# RAY_shield_V4.net
KiCad netlist of a schematic drawn in EAGLE
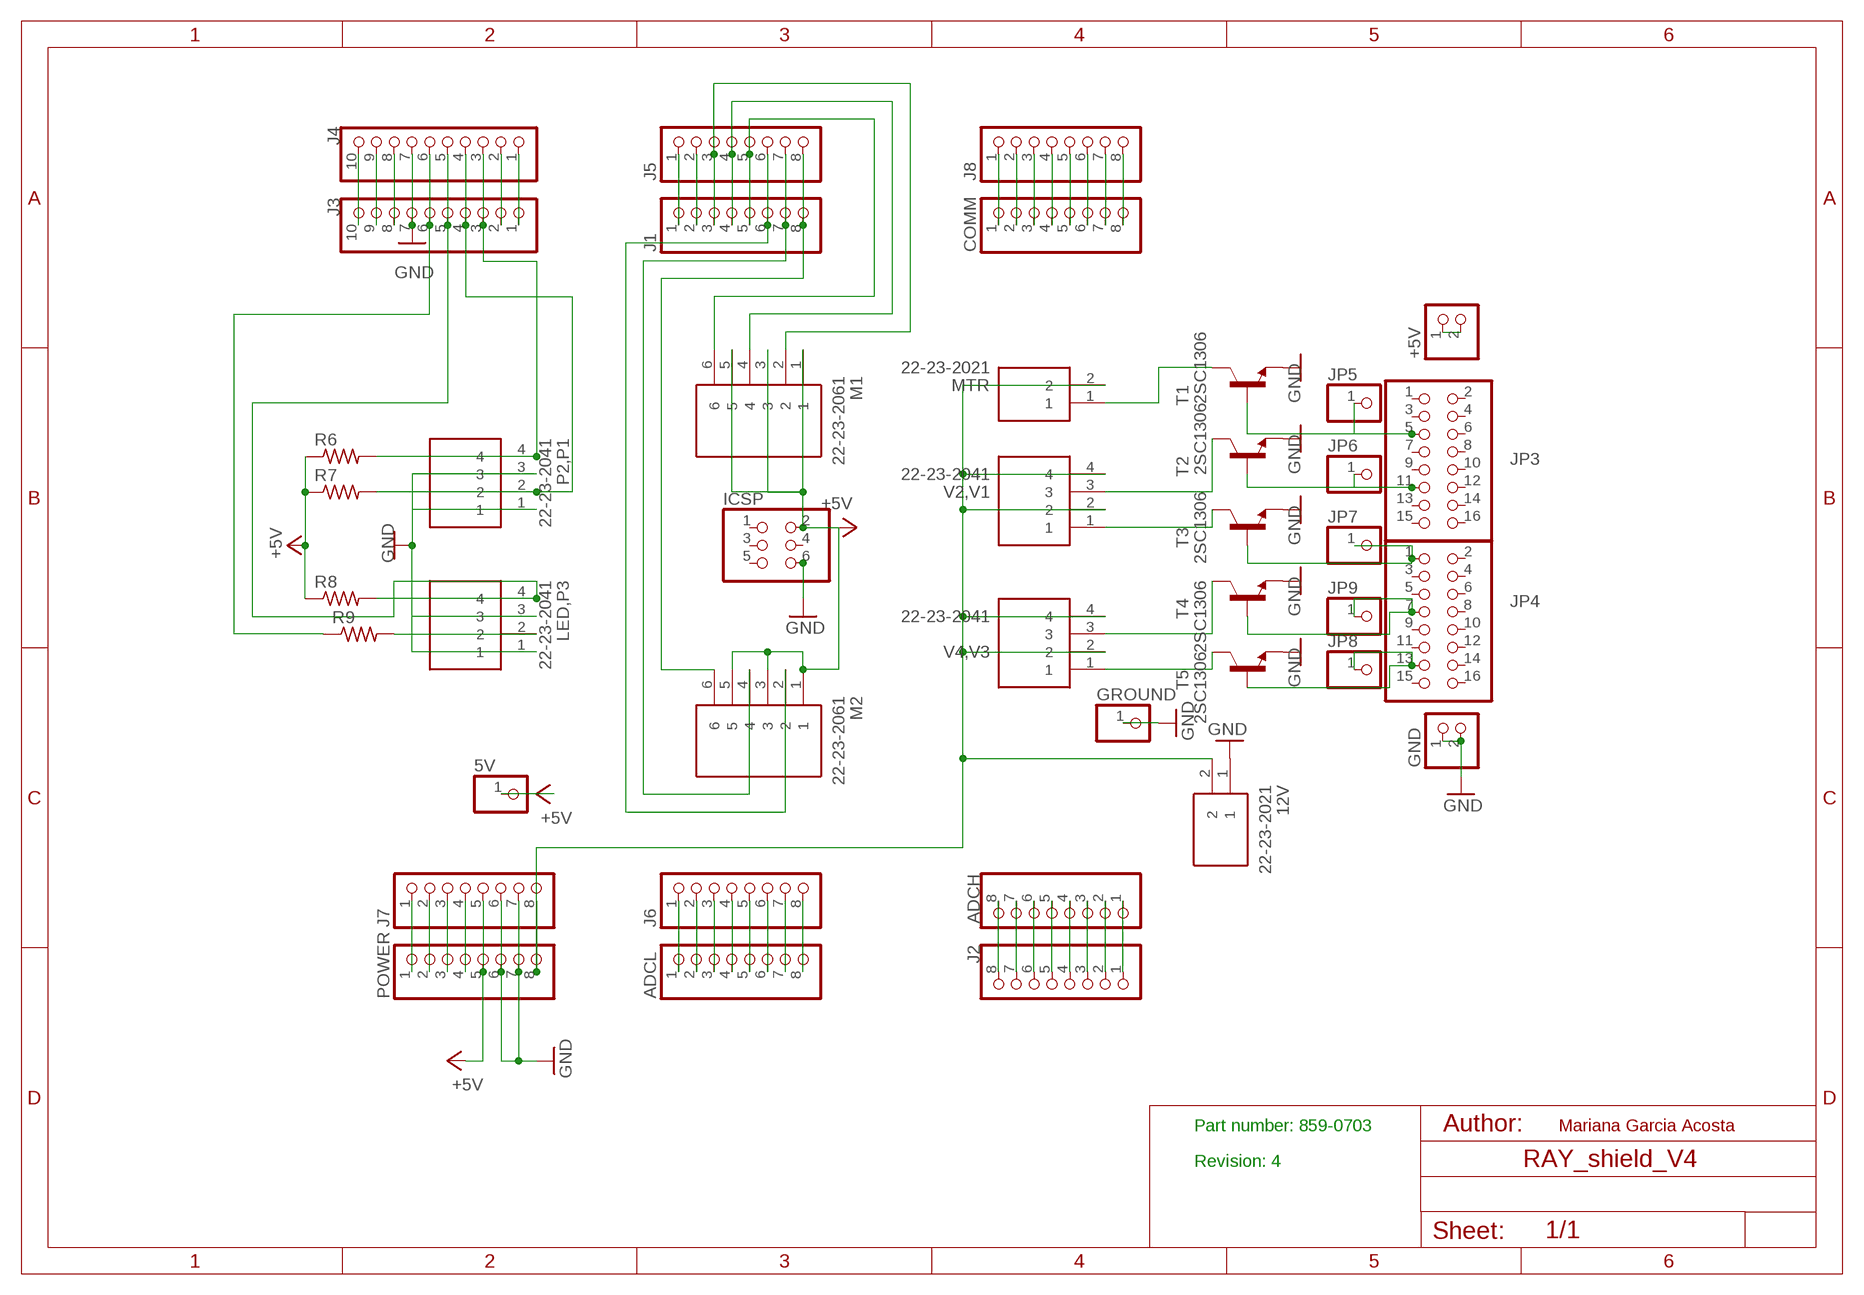
[diagram p0: schematic, sheet 1]

(export (version "E")
  (design (tool "Eeschema 10.0.6"))
  (components
    (comp (ref "+5V")
      (value "PINHD-1X2")
      (footprint "eagle-import:1X02")
      (libsource (lib "eagle-import") (part "PINHD-1X2"))
    )
    (comp (ref "5V")
      (value "PINHD-1X1")
      (footprint "eagle-import:1X01")
      (libsource (lib "eagle-import") (part "PINHD-1X1"))
    )
    (comp (ref "12V")
      (value "22-23-2021")
      (footprint "eagle-import:SHDR2W87P0X254_1X2_493X635X110")
      (fields (field (name "MOUSER_PART_NUMBER") "538-22-23-2021"))
      (libsource (lib "eagle-import") (part "22-23-2021"))
    )
    (comp (ref "ADCH")
      (value "PINHD-1X8TH")
      (footprint "eagle-import:1X08-TH")
      (libsource (lib "eagle-import") (part "PINHD-1X8TH"))
    )
    (comp (ref "ADCL")
      (value "PINHD-1X8TH")
      (footprint "eagle-import:1X08-TH")
      (libsource (lib "eagle-import") (part "PINHD-1X8TH"))
    )
    (comp (ref "COMM")
      (value "PINHD-1X8TH")
      (footprint "eagle-import:1X08-TH")
      (libsource (lib "eagle-import") (part "PINHD-1X8TH"))
    )
    (comp (ref "GND")
      (value "PINHD-1X2")
      (footprint "eagle-import:1X02")
      (libsource (lib "eagle-import") (part "PINHD-1X2"))
    )
    (comp (ref "GROUND")
      (value "PINHD-1X1")
      (footprint "eagle-import:1X01")
      (libsource (lib "eagle-import") (part "PINHD-1X1"))
    )
    (comp (ref "ICSP")
      (value "PINHD-2X3")
      (footprint "eagle-import:2X03")
      (libsource (lib "eagle-import") (part "PINHD-2X3"))
    )
    (comp (ref "J1")
      (value "PINHD-1X8TH")
      (footprint "eagle-import:1X08-TH")
      (libsource (lib "eagle-import") (part "PINHD-1X8TH"))
    )
    (comp (ref "J2")
      (value "PINHD-1X8TH")
      (footprint "eagle-import:1X08-TH")
      (libsource (lib "eagle-import") (part "PINHD-1X8TH"))
    )
    (comp (ref "J3")
      (value "PINHD-1X10TH")
      (footprint "eagle-import:1X10-TH")
      (libsource (lib "eagle-import") (part "PINHD-1X10TH"))
    )
    (comp (ref "J4")
      (value "PINHD-1X10TH")
      (footprint "eagle-import:1X10-TH")
      (libsource (lib "eagle-import") (part "PINHD-1X10TH"))
    )
    (comp (ref "J5")
      (value "PINHD-1X8TH")
      (footprint "eagle-import:1X08-TH")
      (libsource (lib "eagle-import") (part "PINHD-1X8TH"))
    )
    (comp (ref "J6")
      (value "PINHD-1X8TH")
      (footprint "eagle-import:1X08-TH")
      (libsource (lib "eagle-import") (part "PINHD-1X8TH"))
    )
    (comp (ref "J7")
      (value "PINHD-1X8TH")
      (footprint "eagle-import:1X08-TH")
      (libsource (lib "eagle-import") (part "PINHD-1X8TH"))
    )
    (comp (ref "J8")
      (value "PINHD-1X8TH")
      (footprint "eagle-import:1X08-TH")
      (libsource (lib "eagle-import") (part "PINHD-1X8TH"))
    )
    (comp (ref "JP3")
      (value "PINHD-2X8")
      (footprint "eagle-import:2X08")
      (libsource (lib "eagle-import") (part "PINHD-2X8"))
    )
    (comp (ref "JP4")
      (value "PINHD-2X8")
      (footprint "eagle-import:2X08")
      (libsource (lib "eagle-import") (part "PINHD-2X8"))
    )
    (comp (ref "JP5")
      (value "PINHD-1X1")
      (footprint "eagle-import:1X01")
      (libsource (lib "eagle-import") (part "PINHD-1X1"))
    )
    (comp (ref "JP6")
      (value "PINHD-1X1")
      (footprint "eagle-import:1X01")
      (libsource (lib "eagle-import") (part "PINHD-1X1"))
    )
    (comp (ref "JP7")
      (value "PINHD-1X1")
      (footprint "eagle-import:1X01")
      (libsource (lib "eagle-import") (part "PINHD-1X1"))
    )
    (comp (ref "JP8")
      (value "PINHD-1X1")
      (footprint "eagle-import:1X01")
      (libsource (lib "eagle-import") (part "PINHD-1X1"))
    )
    (comp (ref "JP9")
      (value "PINHD-1X1")
      (footprint "eagle-import:1X01")
      (libsource (lib "eagle-import") (part "PINHD-1X1"))
    )
    (comp (ref "LED,P3")
      (value "22-23-2041")
      (footprint "eagle-import:SHDR4W87P0X254_1X4_1001X635X11")
      (fields (field (name "MOUSER_PART_NUMBER") "538-22-23-2041"))
      (libsource (lib "eagle-import") (part "22-23-2041"))
    )
    (comp (ref "M1")
      (value "22-23-2061")
      (footprint "eagle-import:SHDR6W87P0X254_1X6_1509X635X11")
      (fields (field (name "MOUSER_PART_NUMBER") "538-22-23-2061"))
      (libsource (lib "eagle-import") (part "22-23-2061"))
    )
    (comp (ref "M2")
      (value "22-23-2061")
      (footprint "eagle-import:SHDR6W87P0X254_1X6_1509X635X11")
      (fields (field (name "MOUSER_PART_NUMBER") "538-22-23-2061"))
      (libsource (lib "eagle-import") (part "22-23-2061"))
    )
    (comp (ref "MTR")
      (value "22-23-2021")
      (footprint "eagle-import:SHDR2W87P0X254_1X2_493X635X110")
      (fields (field (name "MOUSER_PART_NUMBER") "538-22-23-2021"))
      (libsource (lib "eagle-import") (part "22-23-2021"))
    )
    (comp (ref "P2,P1")
      (value "22-23-2041")
      (footprint "eagle-import:SHDR4W87P0X254_1X4_1001X635X11")
      (fields (field (name "MOUSER_PART_NUMBER") "538-22-23-2041"))
      (libsource (lib "eagle-import") (part "22-23-2041"))
    )
    (comp (ref "POWER")
      (value "PINHD-1X8TH")
      (footprint "eagle-import:1X08-TH")
      (libsource (lib "eagle-import") (part "PINHD-1X8TH"))
    )
    (comp (ref "R6")
      (value "R-US_0207/7")
      (footprint "eagle-import:0207_7")
      (libsource (lib "eagle-import") (part "R-US_0207/7"))
    )
    (comp (ref "R7")
      (value "R-US_0207/7")
      (footprint "eagle-import:0207_7")
      (libsource (lib "eagle-import") (part "R-US_0207/7"))
    )
    (comp (ref "R8")
      (value "R-US_0207/7")
      (footprint "eagle-import:0207_7")
      (libsource (lib "eagle-import") (part "R-US_0207/7"))
    )
    (comp (ref "R9")
      (value "R-US_0207/7")
      (footprint "eagle-import:0207_7")
      (libsource (lib "eagle-import") (part "R-US_0207/7"))
    )
    (comp (ref "T1")
      (value "2SC1306")
      (footprint "eagle-import:TO220BV")
      (libsource (lib "eagle-import") (part "2SC1306"))
    )
    (comp (ref "T2")
      (value "2SC1306")
      (footprint "eagle-import:TO220BV")
      (libsource (lib "eagle-import") (part "2SC1306"))
    )
    (comp (ref "T3")
      (value "2SC1306")
      (footprint "eagle-import:TO220BV")
      (libsource (lib "eagle-import") (part "2SC1306"))
    )
    (comp (ref "T4")
      (value "2SC1306")
      (footprint "eagle-import:TO220BV")
      (libsource (lib "eagle-import") (part "2SC1306"))
    )
    (comp (ref "T5")
      (value "2SC1306")
      (footprint "eagle-import:TO220BV")
      (libsource (lib "eagle-import") (part "2SC1306"))
    )
    (comp (ref "V2,V1")
      (value "22-23-2041")
      (footprint "eagle-import:SHDR4W87P0X254_1X4_1001X635X11")
      (fields (field (name "MOUSER_PART_NUMBER") "538-22-23-2041"))
      (libsource (lib "eagle-import") (part "22-23-2041"))
    )
    (comp (ref "V4,V3")
      (value "22-23-2041")
      (footprint "eagle-import:SHDR4W87P0X254_1X4_1001X635X11")
      (fields (field (name "MOUSER_PART_NUMBER") "538-22-23-2041"))
      (libsource (lib "eagle-import") (part "22-23-2041"))
    )
  )
  (nets
    (net (code "1") (name "+5V") (class "Default")
      (node (ref "5V") (pin "1") (pinfunction "1_1") (pintype "passive"))
      (node (ref "ICSP") (pin "2") (pinfunction "2_2") (pintype "passive"))
      (node (ref "J7") (pin "5") (pinfunction "5_5") (pintype "passive"))
      (node (ref "M1") (pin "1") (pinfunction "1_1") (pintype "bidirectional"))
      (node (ref "M1") (pin "3") (pinfunction "3_3") (pintype "bidirectional"))
      (node (ref "M1") (pin "5") (pinfunction "5_5") (pintype "bidirectional"))
      (node (ref "M2") (pin "1") (pinfunction "1_1") (pintype "bidirectional"))
      (node (ref "M2") (pin "3") (pinfunction "3_3") (pintype "bidirectional"))
      (node (ref "M2") (pin "5") (pinfunction "5_5") (pintype "bidirectional"))
      (node (ref "POWER") (pin "5") (pinfunction "5_5") (pintype "passive"))
      (node (ref "R6") (pin "1") (pinfunction "1_1") (pintype "passive"))
      (node (ref "R7") (pin "1") (pinfunction "1_1") (pintype "passive"))
      (node (ref "R8") (pin "1") (pinfunction "1_1") (pintype "passive"))
    )
    (net (code "2") (name "GND") (class "Default")
      (node (ref "12V") (pin "1") (pinfunction "1_1") (pintype "bidirectional"))
      (node (ref "GND") (pin "1") (pinfunction "1_1") (pintype "passive"))
      (node (ref "GND") (pin "2") (pinfunction "2_2") (pintype "passive"))
      (node (ref "GROUND") (pin "1") (pinfunction "1_1") (pintype "passive"))
      (node (ref "ICSP") (pin "6") (pinfunction "6_6") (pintype "passive"))
      (node (ref "J3") (pin "7") (pinfunction "7_7") (pintype "passive"))
      (node (ref "J4") (pin "7") (pinfunction "7_7") (pintype "passive"))
      (node (ref "J7") (pin "6") (pinfunction "6_6") (pintype "passive"))
      (node (ref "J7") (pin "7") (pinfunction "7_7") (pintype "passive"))
      (node (ref "LED,P3") (pin "1") (pinfunction "1_1") (pintype "bidirectional"))
      (node (ref "LED,P3") (pin "3") (pinfunction "3_3") (pintype "bidirectional"))
      (node (ref "P2,P1") (pin "1") (pinfunction "1_1") (pintype "bidirectional"))
      (node (ref "P2,P1") (pin "3") (pinfunction "3_3") (pintype "bidirectional"))
      (node (ref "POWER") (pin "6") (pinfunction "6_6") (pintype "passive"))
      (node (ref "POWER") (pin "7") (pinfunction "7_7") (pintype "passive"))
      (node (ref "T1") (pin "3") (pinfunction "E_3") (pintype "passive"))
      (node (ref "T2") (pin "3") (pinfunction "E_3") (pintype "passive"))
      (node (ref "T3") (pin "3") (pinfunction "E_3") (pintype "passive"))
      (node (ref "T4") (pin "3") (pinfunction "E_3") (pintype "passive"))
      (node (ref "T5") (pin "3") (pinfunction "E_3") (pintype "passive"))
    )
    (net (code "3") (name "Net-(+5V-Pad1)") (class "Default")
      (node (ref "+5V") (pin "1") (pinfunction "1_1") (pintype "passive"))
      (node (ref "+5V") (pin "2") (pinfunction "2_2") (pintype "passive"))
    )
    (net (code "4") (name "Net-(12V-Pad2)") (class "Default")
      (node (ref "12V") (pin "2") (pinfunction "2_2") (pintype "bidirectional"))
      (node (ref "J7") (pin "8") (pinfunction "8_8") (pintype "passive"))
      (node (ref "MTR") (pin "2") (pinfunction "2_2") (pintype "bidirectional"))
      (node (ref "POWER") (pin "8") (pinfunction "8_8") (pintype "passive"))
      (node (ref "V2,V1") (pin "2") (pinfunction "2_2") (pintype "bidirectional"))
      (node (ref "V2,V1") (pin "4") (pinfunction "4_4") (pintype "bidirectional"))
      (node (ref "V4,V3") (pin "2") (pinfunction "2_2") (pintype "bidirectional"))
      (node (ref "V4,V3") (pin "4") (pinfunction "4_4") (pintype "bidirectional"))
    )
    (net (code "5") (name "Net-(ADCH-Pad1)") (class "Default")
      (node (ref "ADCH") (pin "1") (pinfunction "1_1") (pintype "passive"))
      (node (ref "J2") (pin "1") (pinfunction "1_1") (pintype "passive"))
    )
    (net (code "6") (name "Net-(ADCH-Pad2)") (class "Default")
      (node (ref "ADCH") (pin "2") (pinfunction "2_2") (pintype "passive"))
      (node (ref "J2") (pin "2") (pinfunction "2_2") (pintype "passive"))
    )
    (net (code "7") (name "Net-(ADCH-Pad3)") (class "Default")
      (node (ref "ADCH") (pin "3") (pinfunction "3_3") (pintype "passive"))
      (node (ref "J2") (pin "3") (pinfunction "3_3") (pintype "passive"))
    )
    (net (code "8") (name "Net-(ADCH-Pad4)") (class "Default")
      (node (ref "ADCH") (pin "4") (pinfunction "4_4") (pintype "passive"))
      (node (ref "J2") (pin "4") (pinfunction "4_4") (pintype "passive"))
    )
    (net (code "9") (name "Net-(ADCH-Pad5)") (class "Default")
      (node (ref "ADCH") (pin "5") (pinfunction "5_5") (pintype "passive"))
      (node (ref "J2") (pin "5") (pinfunction "5_5") (pintype "passive"))
    )
    (net (code "10") (name "Net-(ADCH-Pad6)") (class "Default")
      (node (ref "ADCH") (pin "6") (pinfunction "6_6") (pintype "passive"))
      (node (ref "J2") (pin "6") (pinfunction "6_6") (pintype "passive"))
    )
    (net (code "11") (name "Net-(ADCH-Pad7)") (class "Default")
      (node (ref "ADCH") (pin "7") (pinfunction "7_7") (pintype "passive"))
      (node (ref "J2") (pin "7") (pinfunction "7_7") (pintype "passive"))
    )
    (net (code "12") (name "Net-(ADCH-Pad8)") (class "Default")
      (node (ref "ADCH") (pin "8") (pinfunction "8_8") (pintype "passive"))
      (node (ref "J2") (pin "8") (pinfunction "8_8") (pintype "passive"))
    )
    (net (code "13") (name "Net-(ADCL-Pad1)") (class "Default")
      (node (ref "ADCL") (pin "1") (pinfunction "1_1") (pintype "passive"))
      (node (ref "J6") (pin "1") (pinfunction "1_1") (pintype "passive"))
    )
    (net (code "14") (name "Net-(ADCL-Pad2)") (class "Default")
      (node (ref "ADCL") (pin "2") (pinfunction "2_2") (pintype "passive"))
      (node (ref "J6") (pin "2") (pinfunction "2_2") (pintype "passive"))
    )
    (net (code "15") (name "Net-(ADCL-Pad3)") (class "Default")
      (node (ref "ADCL") (pin "3") (pinfunction "3_3") (pintype "passive"))
      (node (ref "J6") (pin "3") (pinfunction "3_3") (pintype "passive"))
    )
    (net (code "16") (name "Net-(ADCL-Pad4)") (class "Default")
      (node (ref "ADCL") (pin "4") (pinfunction "4_4") (pintype "passive"))
      (node (ref "J6") (pin "4") (pinfunction "4_4") (pintype "passive"))
    )
    (net (code "17") (name "Net-(ADCL-Pad5)") (class "Default")
      (node (ref "ADCL") (pin "5") (pinfunction "5_5") (pintype "passive"))
      (node (ref "J6") (pin "5") (pinfunction "5_5") (pintype "passive"))
    )
    (net (code "18") (name "Net-(ADCL-Pad6)") (class "Default")
      (node (ref "ADCL") (pin "6") (pinfunction "6_6") (pintype "passive"))
      (node (ref "J6") (pin "6") (pinfunction "6_6") (pintype "passive"))
    )
    (net (code "19") (name "Net-(ADCL-Pad7)") (class "Default")
      (node (ref "ADCL") (pin "7") (pinfunction "7_7") (pintype "passive"))
      (node (ref "J6") (pin "7") (pinfunction "7_7") (pintype "passive"))
    )
    (net (code "20") (name "Net-(ADCL-Pad8)") (class "Default")
      (node (ref "ADCL") (pin "8") (pinfunction "8_8") (pintype "passive"))
      (node (ref "J6") (pin "8") (pinfunction "8_8") (pintype "passive"))
    )
    (net (code "21") (name "Net-(COMM-Pad1)") (class "Default")
      (node (ref "COMM") (pin "1") (pinfunction "1_1") (pintype "passive"))
      (node (ref "J8") (pin "1") (pinfunction "1_1") (pintype "passive"))
    )
    (net (code "22") (name "Net-(COMM-Pad2)") (class "Default")
      (node (ref "COMM") (pin "2") (pinfunction "2_2") (pintype "passive"))
      (node (ref "J8") (pin "2") (pinfunction "2_2") (pintype "passive"))
    )
    (net (code "23") (name "Net-(COMM-Pad3)") (class "Default")
      (node (ref "COMM") (pin "3") (pinfunction "3_3") (pintype "passive"))
      (node (ref "J8") (pin "3") (pinfunction "3_3") (pintype "passive"))
    )
    (net (code "24") (name "Net-(COMM-Pad4)") (class "Default")
      (node (ref "COMM") (pin "4") (pinfunction "4_4") (pintype "passive"))
      (node (ref "J8") (pin "4") (pinfunction "4_4") (pintype "passive"))
    )
    (net (code "25") (name "Net-(COMM-Pad5)") (class "Default")
      (node (ref "COMM") (pin "5") (pinfunction "5_5") (pintype "passive"))
      (node (ref "J8") (pin "5") (pinfunction "5_5") (pintype "passive"))
    )
    (net (code "26") (name "Net-(COMM-Pad6)") (class "Default")
      (node (ref "COMM") (pin "6") (pinfunction "6_6") (pintype "passive"))
      (node (ref "J8") (pin "6") (pinfunction "6_6") (pintype "passive"))
    )
    (net (code "27") (name "Net-(COMM-Pad7)") (class "Default")
      (node (ref "COMM") (pin "7") (pinfunction "7_7") (pintype "passive"))
      (node (ref "J8") (pin "7") (pinfunction "7_7") (pintype "passive"))
    )
    (net (code "28") (name "Net-(COMM-Pad8)") (class "Default")
      (node (ref "COMM") (pin "8") (pinfunction "8_8") (pintype "passive"))
      (node (ref "J8") (pin "8") (pinfunction "8_8") (pintype "passive"))
    )
    (net (code "29") (name "Net-(J1-Pad1)") (class "Default")
      (node (ref "J1") (pin "1") (pinfunction "1_1") (pintype "passive"))
      (node (ref "J5") (pin "1") (pinfunction "1_1") (pintype "passive"))
    )
    (net (code "30") (name "Net-(J1-Pad2)") (class "Default")
      (node (ref "J1") (pin "2") (pinfunction "2_2") (pintype "passive"))
      (node (ref "J5") (pin "2") (pinfunction "2_2") (pintype "passive"))
    )
    (net (code "31") (name "Net-(J1-Pad3)") (class "Default")
      (node (ref "J1") (pin "3") (pinfunction "3_3") (pintype "passive"))
      (node (ref "J5") (pin "3") (pinfunction "3_3") (pintype "passive"))
      (node (ref "M1") (pin "2") (pinfunction "2_2") (pintype "bidirectional"))
    )
    (net (code "32") (name "Net-(J1-Pad4)") (class "Default")
      (node (ref "J1") (pin "4") (pinfunction "4_4") (pintype "passive"))
      (node (ref "J5") (pin "4") (pinfunction "4_4") (pintype "passive"))
      (node (ref "M1") (pin "4") (pinfunction "4_4") (pintype "bidirectional"))
    )
    (net (code "33") (name "Net-(J1-Pad5)") (class "Default")
      (node (ref "J1") (pin "5") (pinfunction "5_5") (pintype "passive"))
      (node (ref "J5") (pin "5") (pinfunction "5_5") (pintype "passive"))
      (node (ref "M1") (pin "6") (pinfunction "6_6") (pintype "bidirectional"))
    )
    (net (code "34") (name "Net-(J1-Pad6)") (class "Default")
      (node (ref "J1") (pin "6") (pinfunction "6_6") (pintype "passive"))
      (node (ref "J5") (pin "6") (pinfunction "6_6") (pintype "passive"))
      (node (ref "M2") (pin "2") (pinfunction "2_2") (pintype "bidirectional"))
    )
    (net (code "35") (name "Net-(J1-Pad7)") (class "Default")
      (node (ref "J1") (pin "7") (pinfunction "7_7") (pintype "passive"))
      (node (ref "J5") (pin "7") (pinfunction "7_7") (pintype "passive"))
      (node (ref "M2") (pin "4") (pinfunction "4_4") (pintype "bidirectional"))
    )
    (net (code "36") (name "Net-(J1-Pad8)") (class "Default")
      (node (ref "J1") (pin "8") (pinfunction "8_8") (pintype "passive"))
      (node (ref "J5") (pin "8") (pinfunction "8_8") (pintype "passive"))
      (node (ref "M2") (pin "6") (pinfunction "6_6") (pintype "bidirectional"))
    )
    (net (code "37") (name "Net-(J3-Pad1)") (class "Default")
      (node (ref "J3") (pin "1") (pinfunction "1_1") (pintype "passive"))
      (node (ref "J4") (pin "1") (pinfunction "1_1") (pintype "passive"))
    )
    (net (code "38") (name "Net-(J3-Pad2)") (class "Default")
      (node (ref "J3") (pin "2") (pinfunction "2_2") (pintype "passive"))
      (node (ref "J4") (pin "2") (pinfunction "2_2") (pintype "passive"))
    )
    (net (code "39") (name "Net-(J3-Pad3)") (class "Default")
      (node (ref "J3") (pin "3") (pinfunction "3_3") (pintype "passive"))
      (node (ref "J4") (pin "3") (pinfunction "3_3") (pintype "passive"))
      (node (ref "P2,P1") (pin "4") (pinfunction "4_4") (pintype "bidirectional"))
      (node (ref "R6") (pin "2") (pinfunction "2_2") (pintype "passive"))
    )
    (net (code "40") (name "Net-(J3-Pad4)") (class "Default")
      (node (ref "J3") (pin "4") (pinfunction "4_4") (pintype "passive"))
      (node (ref "J4") (pin "4") (pinfunction "4_4") (pintype "passive"))
      (node (ref "P2,P1") (pin "2") (pinfunction "2_2") (pintype "bidirectional"))
      (node (ref "R7") (pin "2") (pinfunction "2_2") (pintype "passive"))
    )
    (net (code "41") (name "Net-(J3-Pad5)") (class "Default")
      (node (ref "J3") (pin "5") (pinfunction "5_5") (pintype "passive"))
      (node (ref "J4") (pin "5") (pinfunction "5_5") (pintype "passive"))
      (node (ref "LED,P3") (pin "4") (pinfunction "4_4") (pintype "bidirectional"))
      (node (ref "R8") (pin "2") (pinfunction "2_2") (pintype "passive"))
    )
    (net (code "42") (name "Net-(J3-Pad6)") (class "Default")
      (node (ref "J3") (pin "6") (pinfunction "6_6") (pintype "passive"))
      (node (ref "J4") (pin "6") (pinfunction "6_6") (pintype "passive"))
      (node (ref "R9") (pin "1") (pinfunction "1_1") (pintype "passive"))
    )
    (net (code "43") (name "Net-(J3-Pad8)") (class "Default")
      (node (ref "J3") (pin "8") (pinfunction "8_8") (pintype "passive"))
      (node (ref "J4") (pin "8") (pinfunction "8_8") (pintype "passive"))
    )
    (net (code "44") (name "Net-(J3-Pad9)") (class "Default")
      (node (ref "J3") (pin "9") (pinfunction "9_9") (pintype "passive"))
      (node (ref "J4") (pin "9") (pinfunction "9_9") (pintype "passive"))
    )
    (net (code "45") (name "Net-(J3-Pad10)") (class "Default")
      (node (ref "J3") (pin "10") (pinfunction "10_10") (pintype "passive"))
      (node (ref "J4") (pin "10") (pinfunction "10_10") (pintype "passive"))
    )
    (net (code "46") (name "Net-(J7-Pad1)") (class "Default")
      (node (ref "J7") (pin "1") (pinfunction "1_1") (pintype "passive"))
      (node (ref "POWER") (pin "1") (pinfunction "1_1") (pintype "passive"))
    )
    (net (code "47") (name "Net-(J7-Pad2)") (class "Default")
      (node (ref "J7") (pin "2") (pinfunction "2_2") (pintype "passive"))
      (node (ref "POWER") (pin "2") (pinfunction "2_2") (pintype "passive"))
    )
    (net (code "48") (name "Net-(J7-Pad3)") (class "Default")
      (node (ref "J7") (pin "3") (pinfunction "3_3") (pintype "passive"))
      (node (ref "POWER") (pin "3") (pinfunction "3_3") (pintype "passive"))
    )
    (net (code "49") (name "Net-(J7-Pad4)") (class "Default")
      (node (ref "J7") (pin "4") (pinfunction "4_4") (pintype "passive"))
      (node (ref "POWER") (pin "4") (pinfunction "4_4") (pintype "passive"))
    )
    (net (code "50") (name "Net-(LED,P3-Pad2)") (class "Default")
      (node (ref "LED,P3") (pin "2") (pinfunction "2_2") (pintype "bidirectional"))
      (node (ref "R9") (pin "2") (pinfunction "2_2") (pintype "passive"))
    )
    (net (code "51") (name "Net-(T1-B)") (class "Default")
      (node (ref "JP3") (pin "5") (pinfunction "5_5") (pintype "passive"))
      (node (ref "JP5") (pin "1") (pinfunction "1_1") (pintype "passive"))
      (node (ref "T1") (pin "1") (pinfunction "B_1") (pintype "passive"))
    )
    (net (code "52") (name "Net-(T1-C)") (class "Default")
      (node (ref "MTR") (pin "1") (pinfunction "1_1") (pintype "bidirectional"))
      (node (ref "T1") (pin "2") (pinfunction "C_2") (pintype "passive"))
    )
    (net (code "53") (name "Net-(T2-B)") (class "Default")
      (node (ref "JP3") (pin "11") (pinfunction "11_11") (pintype "passive"))
      (node (ref "JP6") (pin "1") (pinfunction "1_1") (pintype "passive"))
      (node (ref "T2") (pin "1") (pinfunction "B_1") (pintype "passive"))
    )
    (net (code "54") (name "Net-(T2-C)") (class "Default")
      (node (ref "T2") (pin "2") (pinfunction "C_2") (pintype "passive"))
      (node (ref "V2,V1") (pin "3") (pinfunction "3_3") (pintype "bidirectional"))
    )
    (net (code "55") (name "Net-(T3-B)") (class "Default")
      (node (ref "JP4") (pin "1") (pinfunction "1_1") (pintype "passive"))
      (node (ref "JP7") (pin "1") (pinfunction "1_1") (pintype "passive"))
      (node (ref "T3") (pin "1") (pinfunction "B_1") (pintype "passive"))
    )
    (net (code "56") (name "Net-(T3-C)") (class "Default")
      (node (ref "T3") (pin "2") (pinfunction "C_2") (pintype "passive"))
      (node (ref "V2,V1") (pin "1") (pinfunction "1_1") (pintype "bidirectional"))
    )
    (net (code "57") (name "Net-(T4-B)") (class "Default")
      (node (ref "JP4") (pin "7") (pinfunction "7_7") (pintype "passive"))
      (node (ref "JP9") (pin "1") (pinfunction "1_1") (pintype "passive"))
      (node (ref "T4") (pin "1") (pinfunction "B_1") (pintype "passive"))
    )
    (net (code "58") (name "Net-(T4-C)") (class "Default")
      (node (ref "T4") (pin "2") (pinfunction "C_2") (pintype "passive"))
      (node (ref "V4,V3") (pin "3") (pinfunction "3_3") (pintype "bidirectional"))
    )
    (net (code "59") (name "Net-(T5-B)") (class "Default")
      (node (ref "JP4") (pin "13") (pinfunction "13_13") (pintype "passive"))
      (node (ref "JP8") (pin "1") (pinfunction "1_1") (pintype "passive"))
      (node (ref "T5") (pin "1") (pinfunction "B_1") (pintype "passive"))
    )
    (net (code "60") (name "Net-(T5-C)") (class "Default")
      (node (ref "T5") (pin "2") (pinfunction "C_2") (pintype "passive"))
      (node (ref "V4,V3") (pin "1") (pinfunction "1_1") (pintype "bidirectional"))
    )
    (net (code "61") (name "unconnected-(ICSP-Pad1)") (class "Default")
      (node (ref "ICSP") (pin "1") (pinfunction "1_1") (pintype "passive"))
    )
    (net (code "62") (name "unconnected-(ICSP-Pad3)") (class "Default")
      (node (ref "ICSP") (pin "3") (pinfunction "3_3") (pintype "passive"))
    )
    (net (code "63") (name "unconnected-(ICSP-Pad4)") (class "Default")
      (node (ref "ICSP") (pin "4") (pinfunction "4_4") (pintype "passive"))
    )
    (net (code "64") (name "unconnected-(ICSP-Pad5)") (class "Default")
      (node (ref "ICSP") (pin "5") (pinfunction "5_5") (pintype "passive"))
    )
    (net (code "65") (name "unconnected-(JP3-Pad1)") (class "Default")
      (node (ref "JP3") (pin "1") (pinfunction "1_1") (pintype "passive"))
    )
    (net (code "66") (name "unconnected-(JP3-Pad2)") (class "Default")
      (node (ref "JP3") (pin "2") (pinfunction "2_2") (pintype "passive"))
    )
    (net (code "67") (name "unconnected-(JP3-Pad3)") (class "Default")
      (node (ref "JP3") (pin "3") (pinfunction "3_3") (pintype "passive"))
    )
    (net (code "68") (name "unconnected-(JP3-Pad4)") (class "Default")
      (node (ref "JP3") (pin "4") (pinfunction "4_4") (pintype "passive"))
    )
    (net (code "69") (name "unconnected-(JP3-Pad6)") (class "Default")
      (node (ref "JP3") (pin "6") (pinfunction "6_6") (pintype "passive"))
    )
    (net (code "70") (name "unconnected-(JP3-Pad7)") (class "Default")
      (node (ref "JP3") (pin "7") (pinfunction "7_7") (pintype "passive"))
    )
    (net (code "71") (name "unconnected-(JP3-Pad8)") (class "Default")
      (node (ref "JP3") (pin "8") (pinfunction "8_8") (pintype "passive"))
    )
    (net (code "72") (name "unconnected-(JP3-Pad9)") (class "Default")
      (node (ref "JP3") (pin "9") (pinfunction "9_9") (pintype "passive"))
    )
    (net (code "73") (name "unconnected-(JP3-Pad10)") (class "Default")
      (node (ref "JP3") (pin "10") (pinfunction "10_10") (pintype "passive"))
    )
    (net (code "74") (name "unconnected-(JP3-Pad12)") (class "Default")
      (node (ref "JP3") (pin "12") (pinfunction "12_12") (pintype "passive"))
    )
    (net (code "75") (name "unconnected-(JP3-Pad13)") (class "Default")
      (node (ref "JP3") (pin "13") (pinfunction "13_13") (pintype "passive"))
    )
    (net (code "76") (name "unconnected-(JP3-Pad14)") (class "Default")
      (node (ref "JP3") (pin "14") (pinfunction "14_14") (pintype "passive"))
    )
    (net (code "77") (name "unconnected-(JP3-Pad15)") (class "Default")
      (node (ref "JP3") (pin "15") (pinfunction "15_15") (pintype "passive"))
    )
    (net (code "78") (name "unconnected-(JP3-Pad16)") (class "Default")
      (node (ref "JP3") (pin "16") (pinfunction "16_16") (pintype "passive"))
    )
    (net (code "79") (name "unconnected-(JP4-Pad2)") (class "Default")
      (node (ref "JP4") (pin "2") (pinfunction "2_2") (pintype "passive"))
    )
    (net (code "80") (name "unconnected-(JP4-Pad3)") (class "Default")
      (node (ref "JP4") (pin "3") (pinfunction "3_3") (pintype "passive"))
    )
    (net (code "81") (name "unconnected-(JP4-Pad4)") (class "Default")
      (node (ref "JP4") (pin "4") (pinfunction "4_4") (pintype "passive"))
    )
    (net (code "82") (name "unconnected-(JP4-Pad5)") (class "Default")
      (node (ref "JP4") (pin "5") (pinfunction "5_5") (pintype "passive"))
    )
    (net (code "83") (name "unconnected-(JP4-Pad6)") (class "Default")
      (node (ref "JP4") (pin "6") (pinfunction "6_6") (pintype "passive"))
    )
    (net (code "84") (name "unconnected-(JP4-Pad8)") (class "Default")
      (node (ref "JP4") (pin "8") (pinfunction "8_8") (pintype "passive"))
    )
    (net (code "85") (name "unconnected-(JP4-Pad9)") (class "Default")
      (node (ref "JP4") (pin "9") (pinfunction "9_9") (pintype "passive"))
    )
    (net (code "86") (name "unconnected-(JP4-Pad10)") (class "Default")
      (node (ref "JP4") (pin "10") (pinfunction "10_10") (pintype "passive"))
    )
    (net (code "87") (name "unconnected-(JP4-Pad11)") (class "Default")
      (node (ref "JP4") (pin "11") (pinfunction "11_11") (pintype "passive"))
    )
    (net (code "88") (name "unconnected-(JP4-Pad12)") (class "Default")
      (node (ref "JP4") (pin "12") (pinfunction "12_12") (pintype "passive"))
    )
    (net (code "89") (name "unconnected-(JP4-Pad14)") (class "Default")
      (node (ref "JP4") (pin "14") (pinfunction "14_14") (pintype "passive"))
    )
    (net (code "90") (name "unconnected-(JP4-Pad15)") (class "Default")
      (node (ref "JP4") (pin "15") (pinfunction "15_15") (pintype "passive"))
    )
    (net (code "91") (name "unconnected-(JP4-Pad16)") (class "Default")
      (node (ref "JP4") (pin "16") (pinfunction "16_16") (pintype "passive"))
    )
  )
)
